# Inversor.net
KiCad netlist of a schematic drawn in Altium Designer
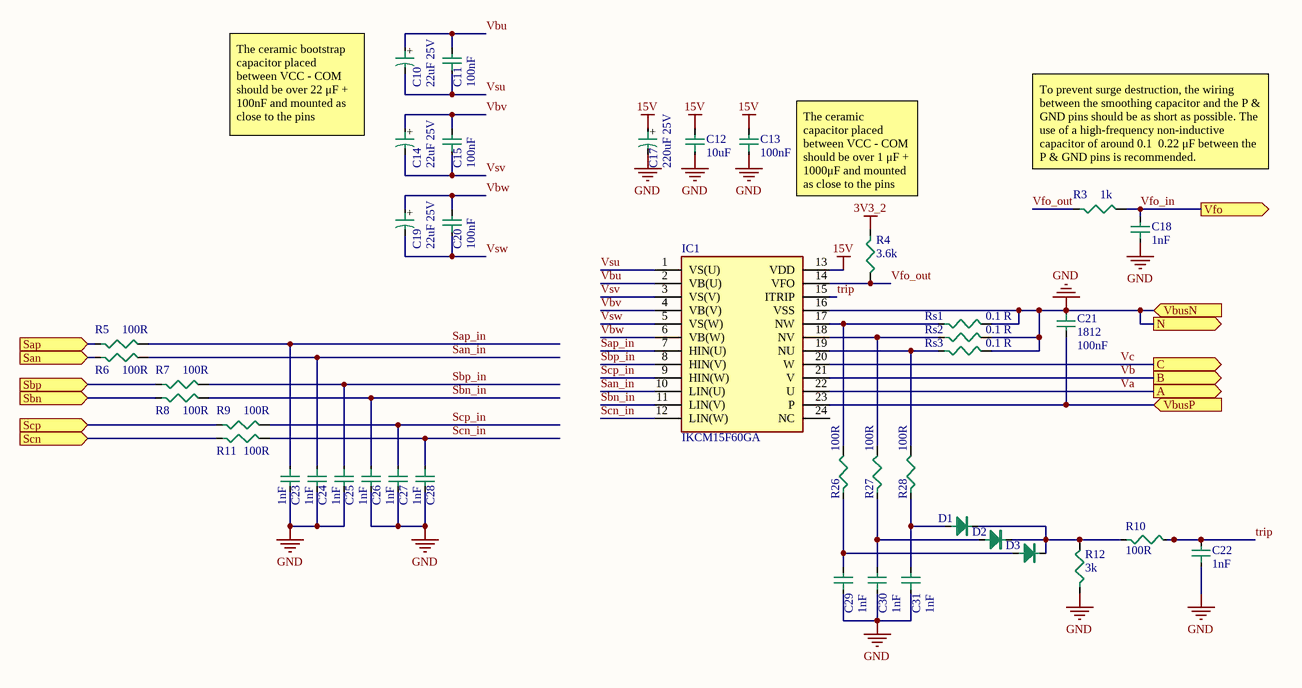
[diagram p0: Inversor.SchDoc]

(export (version "E")
  (design (tool "Eeschema 10.0.6"))
  (components
    (comp (ref "C10")
      (value "22uF 25V")
      (footprint "CAP SMD D5.0 A5.4")
      (description "Capacitor SMD D5.0 A5.4")
      (fields (field (name "Comment") "D5.0 A5.4"))
      (libsource (lib "RLC_Integrated_Library") (part "Capacitor SMD D5.0 A5.4"))
    )
    (comp (ref "C11")
      (value "100nF")
      (footprint "0805C")
      (description "Capacitor SMD 0805")
      (fields (field (name "Comment") "0805"))
      (libsource (lib "RLC_Integrated_Library") (part "Capacitor SMD 0805"))
    )
    (comp (ref "C12")
      (value "10uF")
      (footprint "0805C")
      (description "Capacitor SMD 0805")
      (fields (field (name "Comment") "0805"))
      (libsource (lib "RLC_Integrated_Library") (part "Capacitor SMD 0805"))
    )
    (comp (ref "C13")
      (value "100nF")
      (footprint "0805C")
      (description "Capacitor SMD 0805")
      (fields (field (name "Comment") "0805"))
      (libsource (lib "RLC_Integrated_Library") (part "Capacitor SMD 0805"))
    )
    (comp (ref "C14")
      (value "22uF 25V")
      (footprint "CAP SMD D5.0 A5.4")
      (description "Capacitor SMD D5.0 A5.4")
      (fields (field (name "Comment") "D5.0 A5.4"))
      (libsource (lib "RLC_Integrated_Library") (part "Capacitor SMD D5.0 A5.4"))
    )
    (comp (ref "C15")
      (value "100nF")
      (footprint "0805C")
      (description "Capacitor SMD 0805")
      (fields (field (name "Comment") "0805"))
      (libsource (lib "RLC_Integrated_Library") (part "Capacitor SMD 0805"))
    )
    (comp (ref "C17")
      (value "220uF 25V")
      (footprint "CAP SMD D8.0 A10.2")
      (description "Capacitor SMD D8.0 A10.2")
      (fields (field (name "Comment") "D8.0 A10.2"))
      (libsource (lib "RLC_Integrated_Library") (part "Capacitor SMD D8.0 A10.2"))
    )
    (comp (ref "C18")
      (value "1nF")
      (footprint "0805C")
      (description "Capacitor SMD 0805")
      (fields (field (name "Comment") "0805"))
      (libsource (lib "RLC_Integrated_Library") (part "Capacitor SMD 0805"))
    )
    (comp (ref "C19")
      (value "22uF 25V")
      (footprint "CAP SMD D5.0 A5.4")
      (description "Capacitor SMD D5.0 A5.4")
      (fields (field (name "Comment") "D5.0 A5.4"))
      (libsource (lib "RLC_Integrated_Library") (part "Capacitor SMD D5.0 A5.4"))
    )
    (comp (ref "C20")
      (value "100nF")
      (footprint "0805C")
      (description "Capacitor SMD 0805")
      (fields (field (name "Comment") "0805"))
      (libsource (lib "RLC_Integrated_Library") (part "Capacitor SMD 0805"))
    )
    (comp (ref "C21")
      (value "1812")
      (footprint "1812C")
      (description "Capacitor SMD 1812")
      (fields (field (name "ALTIUM_VALUE") "100nF"))
      (libsource (lib "RLC_Integrated_Library") (part "Capacitor SMD 1812"))
    )
    (comp (ref "C22")
      (value "1nF")
      (footprint "0805C")
      (description "Capacitor SMD 0805")
      (fields (field (name "Comment") "0805"))
      (libsource (lib "RLC_Integrated_Library") (part "Capacitor SMD 0805"))
    )
    (comp (ref "C23")
      (value "1nF")
      (footprint "0805C")
      (description "Capacitor SMD 0805")
      (fields (field (name "Comment") "0805"))
      (libsource (lib "RLC_Integrated_Library") (part "Capacitor SMD 0805"))
    )
    (comp (ref "C24")
      (value "1nF")
      (footprint "0805C")
      (description "Capacitor SMD 0805")
      (fields (field (name "Comment") "0805"))
      (libsource (lib "RLC_Integrated_Library") (part "Capacitor SMD 0805"))
    )
    (comp (ref "C25")
      (value "1nF")
      (footprint "0805C")
      (description "Capacitor SMD 0805")
      (fields (field (name "Comment") "0805"))
      (libsource (lib "RLC_Integrated_Library") (part "Capacitor SMD 0805"))
    )
    (comp (ref "C26")
      (value "1nF")
      (footprint "0805C")
      (description "Capacitor SMD 0805")
      (fields (field (name "Comment") "0805"))
      (libsource (lib "RLC_Integrated_Library") (part "Capacitor SMD 0805"))
    )
    (comp (ref "C27")
      (value "1nF")
      (footprint "0805C")
      (description "Capacitor SMD 0805")
      (fields (field (name "Comment") "0805"))
      (libsource (lib "RLC_Integrated_Library") (part "Capacitor SMD 0805"))
    )
    (comp (ref "C28")
      (value "1nF")
      (footprint "0805C")
      (description "Capacitor SMD 0805")
      (fields (field (name "Comment") "0805"))
      (libsource (lib "RLC_Integrated_Library") (part "Capacitor SMD 0805"))
    )
    (comp (ref "C29")
      (value "1nF")
      (footprint "0805C")
      (description "Capacitor SMD 0805")
      (fields (field (name "Comment") "0805"))
      (libsource (lib "RLC_Integrated_Library") (part "Capacitor SMD 0805"))
    )
    (comp (ref "C30")
      (value "1nF")
      (footprint "0805C")
      (description "Capacitor SMD 0805")
      (fields (field (name "Comment") "0805"))
      (libsource (lib "RLC_Integrated_Library") (part "Capacitor SMD 0805"))
    )
    (comp (ref "C31")
      (value "1nF")
      (footprint "0805C")
      (description "Capacitor SMD 0805")
      (fields (field (name "Comment") "0805"))
      (libsource (lib "RLC_Integrated_Library") (part "Capacitor SMD 0805"))
    )
    (comp (ref "D1")
      (value "1N4148 SMD")
      (footprint "DIODE SMD LL-34")
      (description "Diodo Sinal SMD LL-34")
      (libsource (lib "Diodo_Transistor_Integrated_Library") (part "Diodo Sinal SMD 1N4148"))
    )
    (comp (ref "D2")
      (value "1N4148 SMD")
      (footprint "DIODE SMD LL-34")
      (description "Diodo Sinal SMD LL-34")
      (libsource (lib "Diodo_Transistor_Integrated_Library") (part "Diodo Sinal SMD 1N4148"))
    )
    (comp (ref "D3")
      (value "1N4148 SMD")
      (footprint "DIODE SMD LL-34")
      (description "Diodo Sinal SMD LL-34")
      (libsource (lib "Diodo_Transistor_Integrated_Library") (part "Diodo Sinal SMD 1N4148"))
    )
    (comp (ref "IC1")
      (value "IKCM15F60GA")
      (footprint "INF-CIPOS MINI")
      (description "Integrated Circuit")
      (fields (field (name "MOUSER PART NUMBER") "641-IKCM15F60GA"))
      (libsource (lib "*") (part "IKCM15F60GA"))
    )
    (comp (ref "R3")
      (value "1k")
      (footprint "0805")
      (description "Resistor SMD 0805 1/8 W")
      (fields (field (name "Comment") "0805"))
      (libsource (lib "RLC_Integrated_Library") (part "Resistor SMD 0805 1/8 W"))
    )
    (comp (ref "R4")
      (value "3.6k")
      (footprint "0805")
      (description "Resistor SMD 0805 1/8 W")
      (fields (field (name "Comment") "0805"))
      (libsource (lib "RLC_Integrated_Library") (part "Resistor SMD 0805 1/8 W"))
    )
    (comp (ref "R5")
      (value "100R")
      (footprint "0805")
      (description "Resistor SMD 0805 1/8 W")
      (fields (field (name "Comment") "0805"))
      (libsource (lib "RLC_Integrated_Library") (part "Resistor SMD 0805 1/8 W"))
    )
    (comp (ref "R6")
      (value "100R")
      (footprint "0805")
      (description "Resistor SMD 0805 1/8 W")
      (fields (field (name "Comment") "0805"))
      (libsource (lib "RLC_Integrated_Library") (part "Resistor SMD 0805 1/8 W"))
    )
    (comp (ref "R7")
      (value "100R")
      (footprint "0805")
      (description "Resistor SMD 0805 1/8 W")
      (fields (field (name "Comment") "0805"))
      (libsource (lib "RLC_Integrated_Library") (part "Resistor SMD 0805 1/8 W"))
    )
    (comp (ref "R8")
      (value "100R")
      (footprint "0805")
      (description "Resistor SMD 0805 1/8 W")
      (fields (field (name "Comment") "0805"))
      (libsource (lib "RLC_Integrated_Library") (part "Resistor SMD 0805 1/8 W"))
    )
    (comp (ref "R9")
      (value "100R")
      (footprint "0805")
      (description "Resistor SMD 0805 1/8 W")
      (fields (field (name "Comment") "0805"))
      (libsource (lib "RLC_Integrated_Library") (part "Resistor SMD 0805 1/8 W"))
    )
    (comp (ref "R10")
      (value "100R")
      (footprint "0805")
      (description "Resistor SMD 0805 1/8 W")
      (fields (field (name "Comment") "0805"))
      (libsource (lib "RLC_Integrated_Library") (part "Resistor SMD 0805 1/8 W"))
    )
    (comp (ref "R11")
      (value "100R")
      (footprint "0805")
      (description "Resistor SMD 0805 1/8 W")
      (fields (field (name "Comment") "0805"))
      (libsource (lib "RLC_Integrated_Library") (part "Resistor SMD 0805 1/8 W"))
    )
    (comp (ref "R12")
      (value "3k")
      (footprint "0805")
      (description "Resistor SMD 0805 1/8 W")
      (fields (field (name "Comment") "0805"))
      (libsource (lib "RLC_Integrated_Library") (part "Resistor SMD 0805 1/8 W"))
    )
    (comp (ref "R26")
      (value "100R")
      (footprint "0805")
      (description "Resistor SMD 0805 1/8 W")
      (fields (field (name "Comment") "0805"))
      (libsource (lib "RLC_Integrated_Library") (part "Resistor SMD 0805 1/8 W"))
    )
    (comp (ref "R27")
      (value "100R")
      (footprint "0805")
      (description "Resistor SMD 0805 1/8 W")
      (fields (field (name "Comment") "0805"))
      (libsource (lib "RLC_Integrated_Library") (part "Resistor SMD 0805 1/8 W"))
    )
    (comp (ref "R28")
      (value "100R")
      (footprint "0805")
      (description "Resistor SMD 0805 1/8 W")
      (fields (field (name "Comment") "0805"))
      (libsource (lib "RLC_Integrated_Library") (part "Resistor SMD 0805 1/8 W"))
    )
    (comp (ref "Rs1")
      (value "0.1 R")
      (footprint "CRA2512")
      (description "Resistor SMD 0805 1/8 W")
      (fields (field (name "Comment") "Resistor shunt SMD 3 W"))
      (libsource (lib "RLC_Integrated_Library") (part "Resistor shunt SMD 3 W"))
    )
    (comp (ref "Rs2")
      (value "0.1 R")
      (footprint "CRA2512")
      (description "Resistor SMD 0805 1/8 W")
      (fields (field (name "Comment") "Resistor shunt SMD 3 W"))
      (libsource (lib "RLC_Integrated_Library") (part "Resistor shunt SMD 3 W"))
    )
    (comp (ref "Rs3")
      (value "0.1 R")
      (footprint "CRA2512")
      (description "Resistor SMD 0805 1/8 W")
      (fields (field (name "Comment") "Resistor shunt SMD 3 W"))
      (libsource (lib "RLC_Integrated_Library") (part "Resistor shunt SMD 3 W"))
    )
  )
  (nets
    (net (code "1") (name "/San") (class "Default")
      (node (ref "R6") (pin "1") (pinfunction "1_1") (pintype "passive"))
    )
    (net (code "2") (name "/San_in") (class "Default")
      (node (ref "C24") (pin "1") (pinfunction "1_1") (pintype "passive"))
      (node (ref "IC1") (pin "10") (pinfunction "LIN(U)_10") (pintype "passive"))
      (node (ref "R6") (pin "2") (pinfunction "2_2") (pintype "passive"))
    )
    (net (code "3") (name "/Sap") (class "Default")
      (node (ref "R5") (pin "1") (pinfunction "1_1") (pintype "passive"))
    )
    (net (code "4") (name "/Sap_in") (class "Default")
      (node (ref "C23") (pin "1") (pinfunction "1_1") (pintype "passive"))
      (node (ref "IC1") (pin "7") (pinfunction "HIN(U)_7") (pintype "passive"))
      (node (ref "R5") (pin "2") (pinfunction "2_2") (pintype "passive"))
    )
    (net (code "5") (name "/Sbn") (class "Default")
      (node (ref "R8") (pin "1") (pinfunction "1_1") (pintype "passive"))
    )
    (net (code "6") (name "/Sbn_in") (class "Default")
      (node (ref "C26") (pin "1") (pinfunction "1_1") (pintype "passive"))
      (node (ref "IC1") (pin "11") (pinfunction "LIN(V)_11") (pintype "passive"))
      (node (ref "R8") (pin "2") (pinfunction "2_2") (pintype "passive"))
    )
    (net (code "7") (name "/Sbp") (class "Default")
      (node (ref "R7") (pin "1") (pinfunction "1_1") (pintype "passive"))
    )
    (net (code "8") (name "/Sbp_in") (class "Default")
      (node (ref "C25") (pin "1") (pinfunction "1_1") (pintype "passive"))
      (node (ref "IC1") (pin "8") (pinfunction "HIN(V)_8") (pintype "passive"))
      (node (ref "R7") (pin "2") (pinfunction "2_2") (pintype "passive"))
    )
    (net (code "9") (name "/Scn") (class "Default")
      (node (ref "R11") (pin "1") (pinfunction "1_1") (pintype "passive"))
    )
    (net (code "10") (name "/Scn_in") (class "Default")
      (node (ref "C28") (pin "1") (pinfunction "1_1") (pintype "passive"))
      (node (ref "IC1") (pin "12") (pinfunction "LIN(W)_12") (pintype "passive"))
      (node (ref "R11") (pin "2") (pinfunction "2_2") (pintype "passive"))
    )
    (net (code "11") (name "/Scp") (class "Default")
      (node (ref "R9") (pin "1") (pinfunction "1_1") (pintype "passive"))
    )
    (net (code "12") (name "/Scp_in") (class "Default")
      (node (ref "C27") (pin "1") (pinfunction "1_1") (pintype "passive"))
      (node (ref "IC1") (pin "9") (pinfunction "HIN(W)_9") (pintype "passive"))
      (node (ref "R9") (pin "2") (pinfunction "2_2") (pintype "passive"))
    )
    (net (code "13") (name "/Va") (class "Default")
      (node (ref "IC1") (pin "22") (pinfunction "U_22") (pintype "passive"))
    )
    (net (code "14") (name "/Vb") (class "Default")
      (node (ref "IC1") (pin "21") (pinfunction "V_21") (pintype "passive"))
    )
    (net (code "15") (name "/Vbu") (class "Default")
      (node (ref "C10") (pin "1") (pinfunction "1_1") (pintype "passive"))
      (node (ref "C11") (pin "2") (pinfunction "2_2") (pintype "passive"))
      (node (ref "IC1") (pin "2") (pinfunction "VB(U)_2") (pintype "passive"))
    )
    (net (code "16") (name "/VbusP") (class "Default")
      (node (ref "C21") (pin "2") (pinfunction "2_2") (pintype "passive"))
      (node (ref "IC1") (pin "23") (pinfunction "P_23") (pintype "passive"))
    )
    (net (code "17") (name "/Vbv") (class "Default")
      (node (ref "C14") (pin "1") (pinfunction "1_1") (pintype "passive"))
      (node (ref "C15") (pin "2") (pinfunction "2_2") (pintype "passive"))
      (node (ref "IC1") (pin "4") (pinfunction "VB(V)_4") (pintype "passive"))
    )
    (net (code "18") (name "/Vbw") (class "Default")
      (node (ref "C19") (pin "1") (pinfunction "1_1") (pintype "passive"))
      (node (ref "C20") (pin "2") (pinfunction "2_2") (pintype "passive"))
      (node (ref "IC1") (pin "6") (pinfunction "VB(W)_6") (pintype "passive"))
    )
    (net (code "19") (name "/Vc") (class "Default")
      (node (ref "IC1") (pin "20") (pinfunction "W_20") (pintype "passive"))
    )
    (net (code "20") (name "/Vfo_in") (class "Default")
      (node (ref "C18") (pin "2") (pinfunction "2_2") (pintype "passive"))
      (node (ref "R3") (pin "2") (pinfunction "2_2") (pintype "passive"))
    )
    (net (code "21") (name "/Vfo_out") (class "Default")
      (node (ref "IC1") (pin "14") (pinfunction "VFO_14") (pintype "passive"))
      (node (ref "R3") (pin "1") (pinfunction "1_1") (pintype "passive"))
      (node (ref "R4") (pin "2") (pinfunction "2_2") (pintype "passive"))
    )
    (net (code "22") (name "/Vsu") (class "Default")
      (node (ref "C10") (pin "2") (pinfunction "2_2") (pintype "passive"))
      (node (ref "C11") (pin "1") (pinfunction "1_1") (pintype "passive"))
      (node (ref "IC1") (pin "1") (pinfunction "VS(U)_1") (pintype "passive"))
    )
    (net (code "23") (name "/Vsv") (class "Default")
      (node (ref "C14") (pin "2") (pinfunction "2_2") (pintype "passive"))
      (node (ref "C15") (pin "1") (pinfunction "1_1") (pintype "passive"))
      (node (ref "IC1") (pin "3") (pinfunction "VS(V)_3") (pintype "passive"))
    )
    (net (code "24") (name "/Vsw") (class "Default")
      (node (ref "C19") (pin "2") (pinfunction "2_2") (pintype "passive"))
      (node (ref "C20") (pin "1") (pinfunction "1_1") (pintype "passive"))
      (node (ref "IC1") (pin "5") (pinfunction "VS(W)_5") (pintype "passive"))
    )
    (net (code "25") (name "/trip") (class "Default")
      (node (ref "C22") (pin "2") (pinfunction "2_2") (pintype "passive"))
      (node (ref "IC1") (pin "15") (pinfunction "ITRIP_15") (pintype "passive"))
      (node (ref "R10") (pin "2") (pinfunction "2_2") (pintype "passive"))
    )
    (net (code "26") (name "3V3_2") (class "Default")
      (node (ref "R4") (pin "1") (pinfunction "1_1") (pintype "passive"))
    )
    (net (code "27") (name "15V") (class "Default")
      (node (ref "C12") (pin "2") (pinfunction "2_2") (pintype "passive"))
      (node (ref "C13") (pin "2") (pinfunction "2_2") (pintype "passive"))
      (node (ref "C17") (pin "1") (pinfunction "1_1") (pintype "passive"))
      (node (ref "IC1") (pin "13") (pinfunction "VDD_13") (pintype "passive"))
    )
    (net (code "28") (name "GND") (class "Default")
      (node (ref "C12") (pin "1") (pinfunction "1_1") (pintype "passive"))
      (node (ref "C13") (pin "1") (pinfunction "1_1") (pintype "passive"))
      (node (ref "C17") (pin "2") (pinfunction "2_2") (pintype "passive"))
      (node (ref "C18") (pin "1") (pinfunction "1_1") (pintype "passive"))
      (node (ref "C21") (pin "1") (pinfunction "1_1") (pintype "passive"))
      (node (ref "C22") (pin "1") (pinfunction "1_1") (pintype "passive"))
      (node (ref "C23") (pin "2") (pinfunction "2_2") (pintype "passive"))
      (node (ref "C24") (pin "2") (pinfunction "2_2") (pintype "passive"))
      (node (ref "C25") (pin "2") (pinfunction "2_2") (pintype "passive"))
      (node (ref "C26") (pin "2") (pinfunction "2_2") (pintype "passive"))
      (node (ref "C27") (pin "2") (pinfunction "2_2") (pintype "passive"))
      (node (ref "C28") (pin "2") (pinfunction "2_2") (pintype "passive"))
      (node (ref "C29") (pin "1") (pinfunction "1_1") (pintype "passive"))
      (node (ref "C30") (pin "1") (pinfunction "1_1") (pintype "passive"))
      (node (ref "C31") (pin "1") (pinfunction "1_1") (pintype "passive"))
      (node (ref "IC1") (pin "16") (pinfunction "VSS_16") (pintype "passive"))
      (node (ref "R12") (pin "1") (pinfunction "1_1") (pintype "passive"))
      (node (ref "Rs1") (pin "2") (pinfunction "2_2") (pintype "passive"))
      (node (ref "Rs2") (pin "2") (pinfunction "2_2") (pintype "passive"))
      (node (ref "Rs3") (pin "2") (pinfunction "2_2") (pintype "passive"))
    )
    (net (code "29") (name "Net-(C29-Pad2)") (class "Default")
      (node (ref "C29") (pin "2") (pinfunction "2_2") (pintype "passive"))
      (node (ref "D3") (pin "A") (pinfunction "A_A") (pintype "passive"))
      (node (ref "R26") (pin "1") (pinfunction "1_1") (pintype "passive"))
    )
    (net (code "30") (name "Net-(C30-Pad2)") (class "Default")
      (node (ref "C30") (pin "2") (pinfunction "2_2") (pintype "passive"))
      (node (ref "D2") (pin "A") (pinfunction "A_A") (pintype "passive"))
      (node (ref "R27") (pin "1") (pinfunction "1_1") (pintype "passive"))
    )
    (net (code "31") (name "Net-(C31-Pad2)") (class "Default")
      (node (ref "C31") (pin "2") (pinfunction "2_2") (pintype "passive"))
      (node (ref "D1") (pin "A") (pinfunction "A_A") (pintype "passive"))
      (node (ref "R28") (pin "1") (pinfunction "1_1") (pintype "passive"))
    )
    (net (code "32") (name "Net-(D1-PadK)") (class "Default")
      (node (ref "D1") (pin "K") (pinfunction "K_K") (pintype "passive"))
      (node (ref "D2") (pin "K") (pinfunction "K_K") (pintype "passive"))
      (node (ref "D3") (pin "K") (pinfunction "K_K") (pintype "passive"))
      (node (ref "R10") (pin "1") (pinfunction "1_1") (pintype "passive"))
      (node (ref "R12") (pin "2") (pinfunction "2_2") (pintype "passive"))
    )
    (net (code "33") (name "Net-(IC1-NU)") (class "Default")
      (node (ref "IC1") (pin "19") (pinfunction "NU_19") (pintype "passive"))
      (node (ref "R28") (pin "2") (pinfunction "2_2") (pintype "passive"))
      (node (ref "Rs3") (pin "1") (pinfunction "1_1") (pintype "passive"))
    )
    (net (code "34") (name "Net-(IC1-NV)") (class "Default")
      (node (ref "IC1") (pin "18") (pinfunction "NV_18") (pintype "passive"))
      (node (ref "R27") (pin "2") (pinfunction "2_2") (pintype "passive"))
      (node (ref "Rs2") (pin "1") (pinfunction "1_1") (pintype "passive"))
    )
    (net (code "35") (name "Net-(IC1-NW)") (class "Default")
      (node (ref "IC1") (pin "17") (pinfunction "NW_17") (pintype "passive"))
      (node (ref "R26") (pin "2") (pinfunction "2_2") (pintype "passive"))
      (node (ref "Rs1") (pin "1") (pinfunction "1_1") (pintype "passive"))
    )
    (net (code "36") (name "unconnected-(IC1-NC-Pad24)") (class "Default")
      (node (ref "IC1") (pin "24") (pinfunction "NC_24") (pintype "passive"))
    )
  )
)
